# ProPrj.net
KiCad netlist of a schematic drawn in EasyEDA Pro
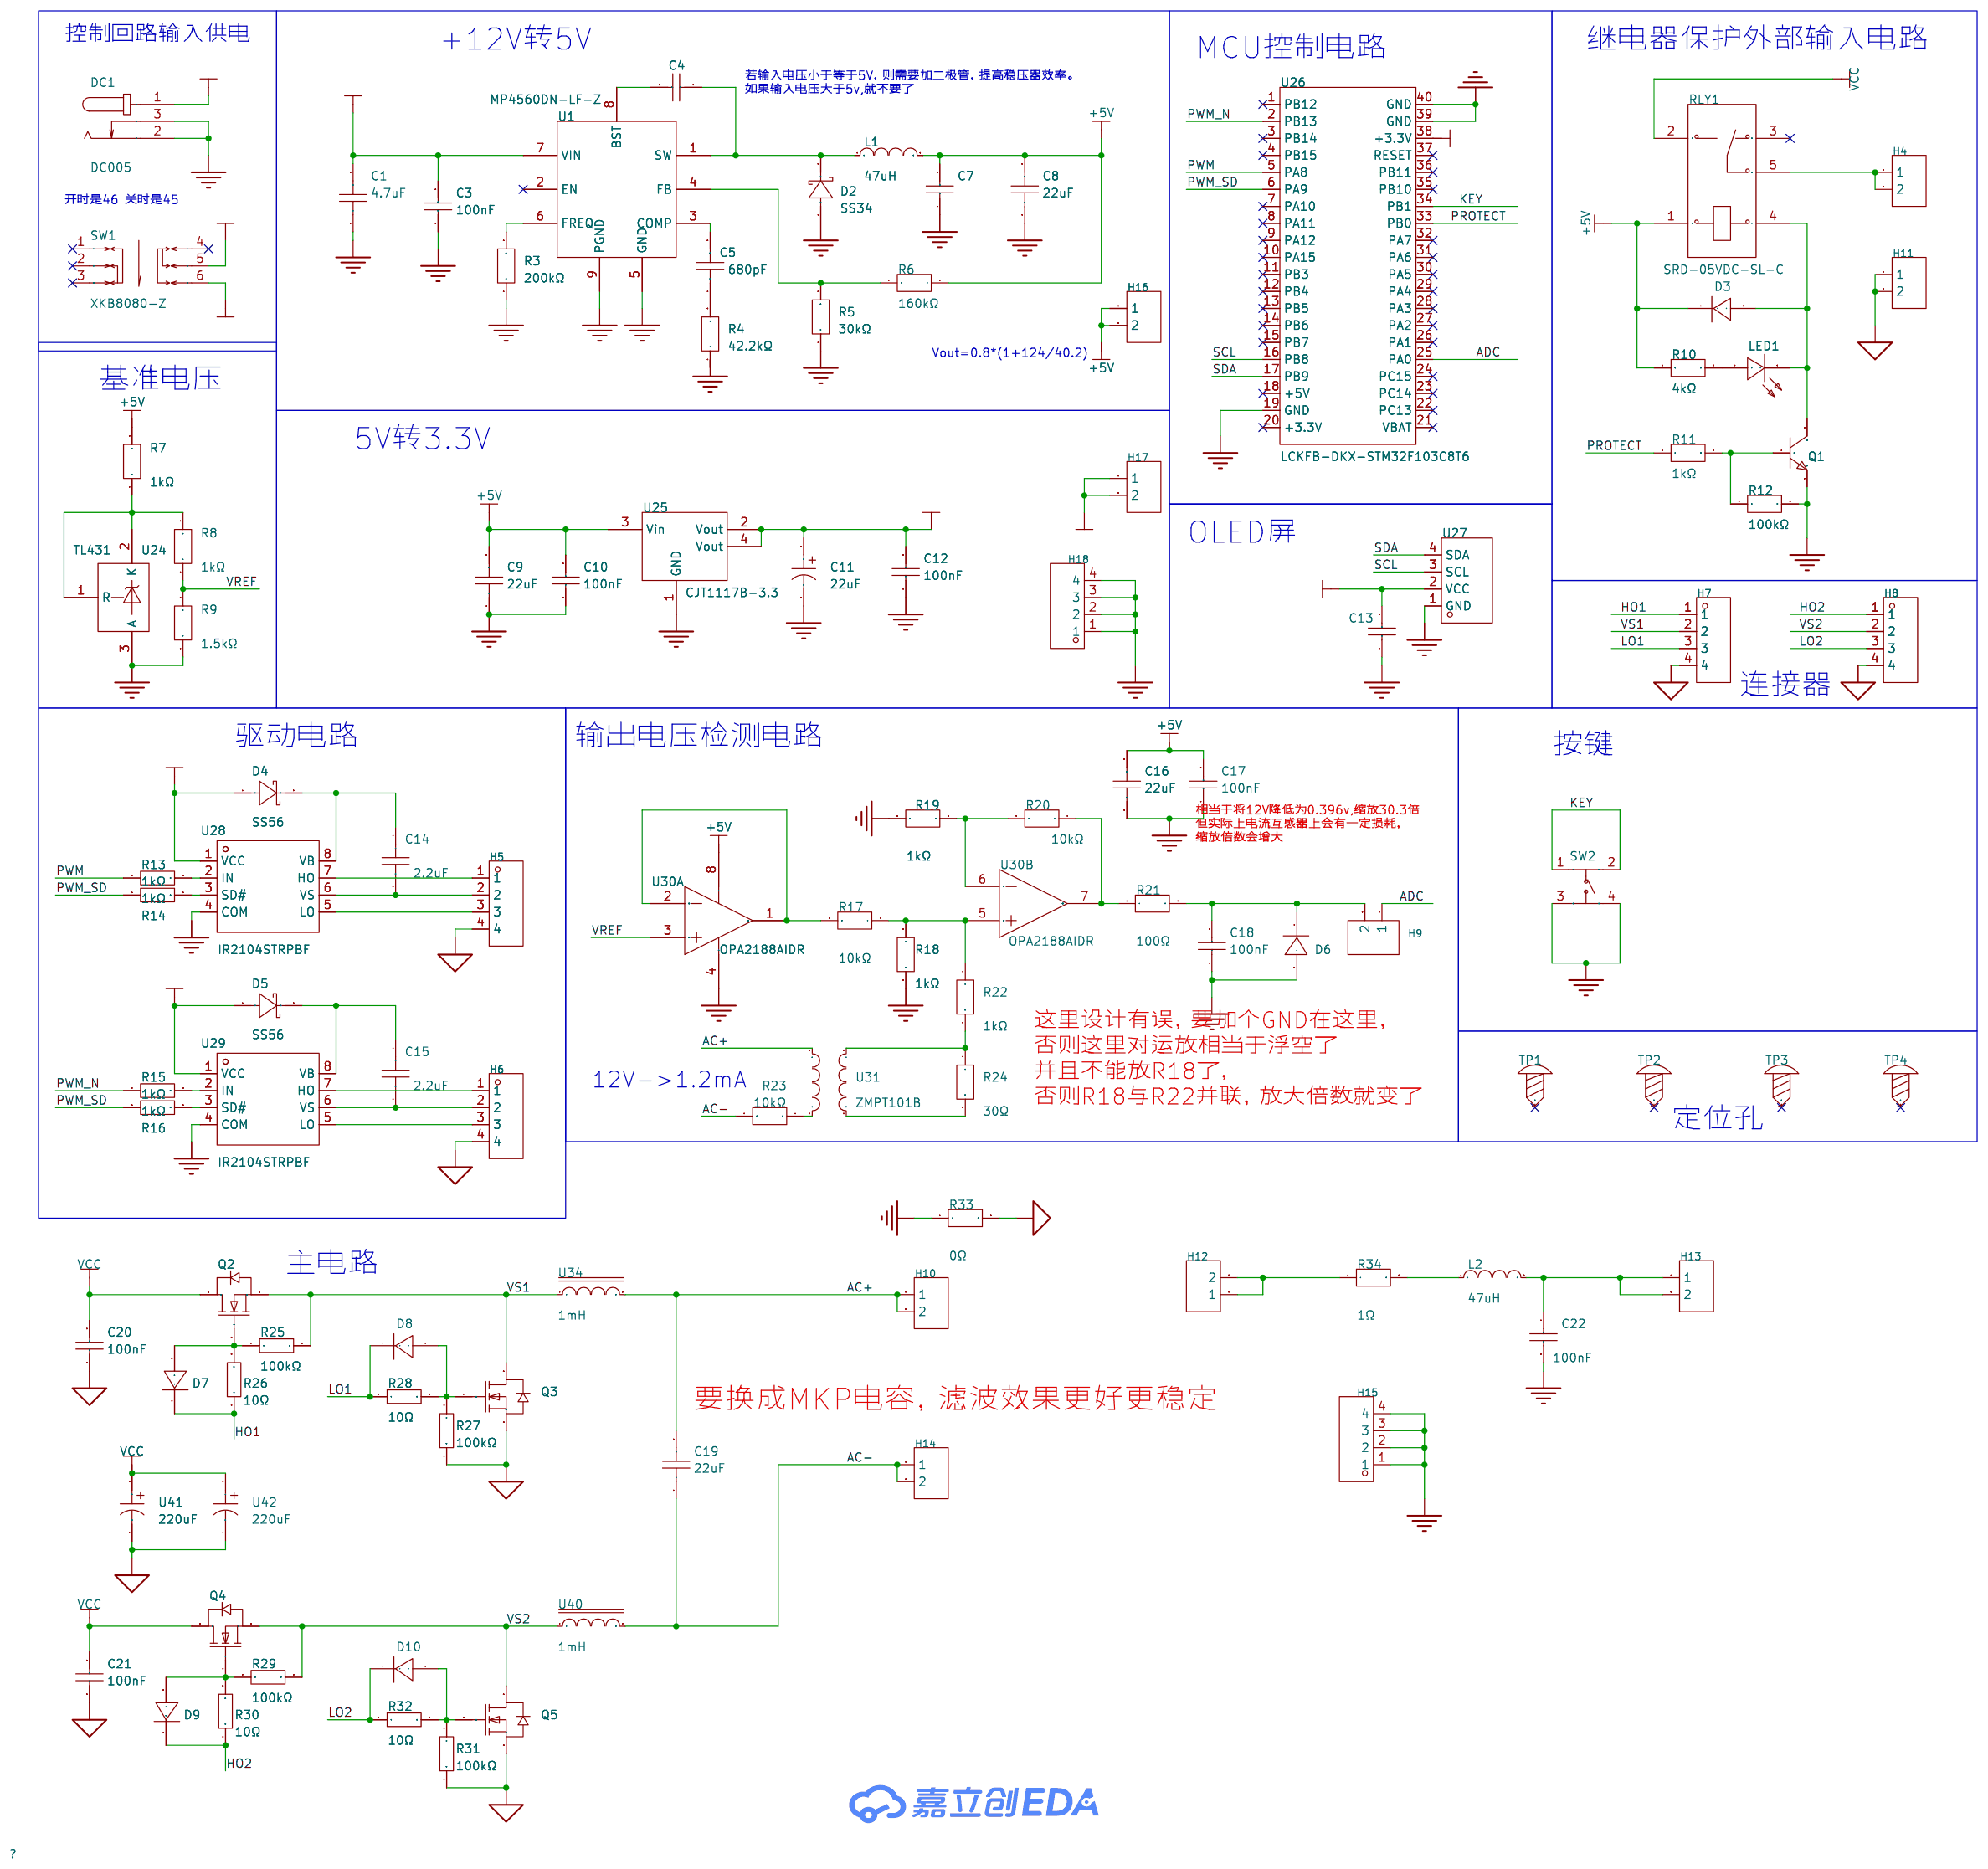
[diagram p0: schematic sheet]

(export (version "E")
  (design (tool "Eeschema 10.0.6"))
  (components
    (comp (ref "C1")
      (value "4.7uF")
      (footprint "easyedapro:C1206")
      (description "容值:4.7uF;精度:±10%;额定电压:100V;温度系数:X7R;")
      (fields
        (field (name "Manufacturer Part") "HHV1206R7475K101NSPJ")
        (field (name "Manufacturer") "Chinocera(华瓷)")
      )
      (libsource (lib "easyedapro") (part "HHV1206R7475K101NSPJ"))
    )
    (comp (ref "C3")
      (value "100nF")
      (footprint "easyedapro:C0805")
      (description "容值:100nF;精度:±10%;额定电压:100V;温度系数:X7R;")
      (fields
        (field (name "Manufacturer Part") "CL21B104KCFNNNE")
        (field (name "Manufacturer") "SAMSUNG(三星)")
      )
      (libsource (lib "easyedapro") (part "CL21B104KCFNNNE"))
    )
    (comp (ref "C4")
      (value "100nF")
      (footprint "easyedapro:C0805")
      (description "容值:100nF;精度:±10%;额定电压:100V;温度系数:X7R;")
      (fields
        (field (name "Manufacturer Part") "CL21B104KCFNNNE")
        (field (name "Manufacturer") "SAMSUNG(三星)")
      )
      (libsource (lib "easyedapro") (part "CL21B104KCFNNNE"))
    )
    (comp (ref "C5")
      (value "680pF")
      (footprint "easyedapro:C0805")
      (description "容值:680pF;精度:±10%;额定电压:100V;温度系数:X7R;")
      (fields
        (field (name "Manufacturer Part") "HHV0805R7681K101NTHJ")
        (field (name "Manufacturer") "Chinocera(华瓷)")
      )
      (libsource (lib "easyedapro") (part "HHV0805R7681K101NTHJ"))
    )
    (comp (ref "C7")
      (value "100nF")
      (footprint "easyedapro:C0805")
      (description "容值:100nF;精度:±10%;额定电压:100V;温度系数:X7R;")
      (fields
        (field (name "Manufacturer Part") "CL21B104KCFNNNE")
        (field (name "Manufacturer") "SAMSUNG(三星)")
      )
      (libsource (lib "easyedapro") (part "CL21B104KCFNNNE"))
    )
    (comp (ref "C8")
      (value "22uF")
      (footprint "easyedapro:C0805")
      (description "容值:22uF;精度:±20%;额定电压:35V;材质(温度系数):X5R;")
      (fields
        (field (name "Manufacturer Part") "CGA0805X5R226M350MT")
        (field (name "Manufacturer") "HRE(芯声)")
      )
      (libsource (lib "easyedapro") (part "CGA0805X5R226M350MT"))
    )
    (comp (ref "C9")
      (value "22uF")
      (footprint "easyedapro:C0805")
      (description "容值:22uF;精度:±20%;额定电压:35V;材质(温度系数):X5R;")
      (fields
        (field (name "Manufacturer Part") "CGA0805X5R226M350MT")
        (field (name "Manufacturer") "HRE(芯声)")
      )
      (libsource (lib "easyedapro") (part "CGA0805X5R226M350MT"))
    )
    (comp (ref "C10")
      (value "100nF")
      (footprint "easyedapro:C0805")
      (description "容值:100nF;精度:±10%;额定电压:100V;温度系数:X7R;")
      (fields
        (field (name "Manufacturer Part") "CL21B104KCFNNNE")
        (field (name "Manufacturer") "SAMSUNG(三星)")
      )
      (libsource (lib "easyedapro") (part "CL21B104KCFNNNE"))
    )
    (comp (ref "C11")
      (value "22uF")
      (footprint "easyedapro:CAP-TH_BD6.0-P2.54-D0.5-FD")
      (description "容值:22uF;精度:±10%;额定电压:25V;等效串联电阻(ESR):-;")
      (fields
        (field (name "Manufacturer Part") "199D226X9025D1V1E3")
        (field (name "Manufacturer") "VISHAY(威世)")
      )
      (libsource (lib "easyedapro") (part "199D226X9025D1V1E3"))
    )
    (comp (ref "C12")
      (value "100nF")
      (footprint "easyedapro:C0805")
      (description "容值:100nF;精度:±10%;额定电压:100V;温度系数:X7R;")
      (fields
        (field (name "Manufacturer Part") "CL21B104KCFNNNE")
        (field (name "Manufacturer") "SAMSUNG(三星)")
      )
      (libsource (lib "easyedapro") (part "CL21B104KCFNNNE"))
    )
    (comp (ref "C13")
      (value "100nF")
      (footprint "easyedapro:C0805")
      (description "容值:100nF;精度:±10%;额定电压:100V;温度系数:X7R;")
      (fields
        (field (name "Manufacturer Part") "CL21B104KCFNNNE")
        (field (name "Manufacturer") "SAMSUNG(三星)")
      )
      (libsource (lib "easyedapro") (part "CL21B104KCFNNNE"))
    )
    (comp (ref "C14")
      (value "2.2uF")
      (footprint "easyedapro:C0805")
      (description "容值:22uF;精度:±20%;额定电压:35V;材质(温度系数):X5R;")
      (fields
        (field (name "Manufacturer Part") "CGA0805X5R226M350MT")
        (field (name "Manufacturer") "HRE(芯声)")
      )
      (libsource (lib "easyedapro") (part "CGA0805X5R226M350MT"))
    )
    (comp (ref "C15")
      (value "2.2uF")
      (footprint "easyedapro:C0805")
      (description "容值:22uF;精度:±20%;额定电压:35V;材质(温度系数):X5R;")
      (fields
        (field (name "Manufacturer Part") "CGA0805X5R226M350MT")
        (field (name "Manufacturer") "HRE(芯声)")
      )
      (libsource (lib "easyedapro") (part "CGA0805X5R226M350MT"))
    )
    (comp (ref "C16")
      (value "22uF")
      (footprint "easyedapro:C0805")
      (description "容值:22uF;精度:±20%;额定电压:35V;材质(温度系数):X5R;")
      (fields
        (field (name "Manufacturer Part") "CGA0805X5R226M350MT")
        (field (name "Manufacturer") "HRE(芯声)")
      )
      (libsource (lib "easyedapro") (part "CGA0805X5R226M350MT"))
    )
    (comp (ref "C17")
      (value "100nF")
      (footprint "easyedapro:C0805")
      (description "容值:100nF;精度:±10%;额定电压:100V;温度系数:X7R;")
      (fields
        (field (name "Manufacturer Part") "CL21B104KCFNNNE")
        (field (name "Manufacturer") "SAMSUNG(三星)")
      )
      (libsource (lib "easyedapro") (part "CL21B104KCFNNNE"))
    )
    (comp (ref "C18")
      (value "100nF")
      (footprint "easyedapro:C0805")
      (description "容值:100nF;精度:±10%;额定电压:100V;温度系数:X7R;")
      (fields
        (field (name "Manufacturer Part") "CL21B104KCFNNNE")
        (field (name "Manufacturer") "SAMSUNG(三星)")
      )
      (libsource (lib "easyedapro") (part "CL21B104KCFNNNE"))
    )
    (comp (ref "C19")
      (value "22uF")
      (footprint "easyedapro:C0805")
      (description "容值:22uF;精度:±20%;额定电压:35V;材质(温度系数):X5R;")
      (fields
        (field (name "Manufacturer Part") "CGA0805X5R226M350MT")
        (field (name "Manufacturer") "HRE(芯声)")
      )
      (libsource (lib "easyedapro") (part "CGA0805X5R226M350MT"))
    )
    (comp (ref "C20")
      (value "100nF")
      (footprint "easyedapro:C0805")
      (description "容值:100nF;精度:±10%;额定电压:100V;温度系数:X7R;")
      (fields
        (field (name "Manufacturer Part") "CL21B104KCFNNNE")
        (field (name "Manufacturer") "SAMSUNG(三星)")
      )
      (libsource (lib "easyedapro") (part "CL21B104KCFNNNE"))
    )
    (comp (ref "C21")
      (value "100nF")
      (footprint "easyedapro:C0805")
      (description "容值:100nF;精度:±10%;额定电压:100V;温度系数:X7R;")
      (fields
        (field (name "Manufacturer Part") "CL21B104KCFNNNE")
        (field (name "Manufacturer") "SAMSUNG(三星)")
      )
      (libsource (lib "easyedapro") (part "CL21B104KCFNNNE"))
    )
    (comp (ref "C22")
      (value "100nF")
      (footprint "easyedapro:C0805")
      (description "容值:100nF;精度:±10%;额定电压:100V;温度系数:X7R;")
      (fields
        (field (name "Manufacturer Part") "CL21B104KCFNNNE")
        (field (name "Manufacturer") "SAMSUNG(三星)")
      )
      (libsource (lib "easyedapro") (part "CL21B104KCFNNNE"))
    )
    (comp (ref "D2")
      (value "SS34")
      (footprint "easyedapro:SMA_L4.3-W2.6-LS5.0-FD")
      (description "二极管配置:独立式;正向压降(Vf):550mV@3.0A;直流反向耐压(Vr):40V;整流电流:3A;")
      (fields (field (name "Manufacturer") "R+O(宏嘉诚)"))
      (libsource (lib "easyedapro") (part "SS34_C7420365"))
    )
    (comp (ref "D3")
      (value "1N4148W-E3-08")
      (footprint "easyedapro:SOD-123_L2.8-W1.8-LS3.7-RD")
      (description "二极管配置:1个独立式;正向压降(Vf):1.2V@100mA;直流反向耐压(Vr):75V;整流电流:150mA;反向恢复时间(Trr):4ns;")
      (fields (field (name "Manufacturer") "VISHAY(威世)"))
      (libsource (lib "easyedapro") (part "1N4148W-E3-08"))
    )
    (comp (ref "D4")
      (value "SS56")
      (footprint "easyedapro:SMA_L4.3-W2.6-LS5.0-FD")
      (description "二极管配置:独立式;正向压降(Vf):550mV@3.0A;直流反向耐压(Vr):40V;整流电流:3A;")
      (fields (field (name "Manufacturer") "R+O(宏嘉诚)"))
      (libsource (lib "easyedapro") (part "SS34_C7420365"))
    )
    (comp (ref "D5")
      (value "SS56")
      (footprint "easyedapro:SMA_L4.3-W2.6-LS5.0-FD")
      (description "二极管配置:独立式;正向压降(Vf):550mV@3.0A;直流反向耐压(Vr):40V;整流电流:3A;")
      (fields (field (name "Manufacturer") "R+O(宏嘉诚)"))
      (libsource (lib "easyedapro") (part "SS34_C7420365"))
    )
    (comp (ref "D6")
      (value "1N4148W-E3-08")
      (footprint "easyedapro:SOD-123_L2.8-W1.8-LS3.7-RD")
      (description "二极管配置:1个独立式;正向压降(Vf):1.2V@100mA;直流反向耐压(Vr):75V;整流电流:150mA;反向恢复时间(Trr):4ns;")
      (fields (field (name "Manufacturer") "VISHAY(威世)"))
      (libsource (lib "easyedapro") (part "1N4148W-E3-08"))
    )
    (comp (ref "D7")
      (value "1N4148W-E3-08")
      (footprint "easyedapro:SOD-123_L2.8-W1.8-LS3.7-RD")
      (description "二极管配置:1个独立式;正向压降(Vf):1.2V@100mA;直流反向耐压(Vr):75V;整流电流:150mA;反向恢复时间(Trr):4ns;")
      (fields (field (name "Manufacturer") "VISHAY(威世)"))
      (libsource (lib "easyedapro") (part "1N4148W-E3-08"))
    )
    (comp (ref "D8")
      (value "1N4148W-E3-08")
      (footprint "easyedapro:SOD-123_L2.8-W1.8-LS3.7-RD")
      (description "二极管配置:1个独立式;正向压降(Vf):1.2V@100mA;直流反向耐压(Vr):75V;整流电流:150mA;反向恢复时间(Trr):4ns;")
      (fields (field (name "Manufacturer") "VISHAY(威世)"))
      (libsource (lib "easyedapro") (part "1N4148W-E3-08"))
    )
    (comp (ref "D9")
      (value "1N4148W-E3-08")
      (footprint "easyedapro:SOD-123_L2.8-W1.8-LS3.7-RD")
      (description "二极管配置:1个独立式;正向压降(Vf):1.2V@100mA;直流反向耐压(Vr):75V;整流电流:150mA;反向恢复时间(Trr):4ns;")
      (fields (field (name "Manufacturer") "VISHAY(威世)"))
      (libsource (lib "easyedapro") (part "1N4148W-E3-08"))
    )
    (comp (ref "D10")
      (value "1N4148W-E3-08")
      (footprint "easyedapro:SOD-123_L2.8-W1.8-LS3.7-RD")
      (description "二极管配置:1个独立式;正向压降(Vf):1.2V@100mA;直流反向耐压(Vr):75V;整流电流:150mA;反向恢复时间(Trr):4ns;")
      (fields (field (name "Manufacturer") "VISHAY(威世)"))
      (libsource (lib "easyedapro") (part "1N4148W-E3-08"))
    )
    (comp (ref "DC1")
      (value "DC005")
      (footprint "easyedapro:DC-IN-TH_DC005")
      (description "连接器类型:DC电源插座;安装方式:弯插;触点内径:2mm;触点外径:6.3mm;额定电流:500mA;额定电压:30V;工作温度:-25°C~+70°C;")
      (fields (field (name "Manufacturer") "SHOU HAN(首韩)"))
      (libsource (lib "easyedapro") (part "DC005_C431533"))
    )
    (comp (ref "H4")
      (value "~")
      (footprint "easyedapro:HDR-TH_2P-P2.54-V-F")
      (libsource (lib "easyedapro") (part "Header-Female-2.54_1x2"))
    )
    (comp (ref "H5")
      (value "~")
      (footprint "easyedapro:HDR-TH_4P-P2.54-V-F")
      (libsource (lib "easyedapro") (part "2.54-1*4P母"))
    )
    (comp (ref "H6")
      (value "~")
      (footprint "easyedapro:HDR-TH_4P-P2.54-V-F")
      (libsource (lib "easyedapro") (part "2.54-1*4P母"))
    )
    (comp (ref "H7")
      (value "~")
      (footprint "easyedapro:HDR-TH_4P-P2.54-V-F")
      (libsource (lib "easyedapro") (part "2.54-1*4P母"))
    )
    (comp (ref "H8")
      (value "~")
      (footprint "easyedapro:HDR-TH_4P-P2.54-V-F")
      (libsource (lib "easyedapro") (part "2.54-1*4P母"))
    )
    (comp (ref "H9")
      (value "~")
      (footprint "easyedapro:HDR-TH_2P-P2.54-V-F")
      (libsource (lib "easyedapro") (part "Header-Female-2.54_1x2"))
    )
    (comp (ref "H10")
      (value "~")
      (footprint "easyedapro:HDR-TH_2P-P2.54-V-F")
      (libsource (lib "easyedapro") (part "Header-Female-2.54_1x2"))
    )
    (comp (ref "H11")
      (value "~")
      (footprint "easyedapro:HDR-TH_2P-P2.54-V-F")
      (libsource (lib "easyedapro") (part "Header-Female-2.54_1x2"))
    )
    (comp (ref "H12")
      (value "~")
      (footprint "easyedapro:HDR-TH_2P-P2.54-V-F")
      (libsource (lib "easyedapro") (part "Header-Female-2.54_1x2"))
    )
    (comp (ref "H13")
      (value "~")
      (footprint "easyedapro:HDR-TH_2P-P2.54-V-F")
      (libsource (lib "easyedapro") (part "Header-Female-2.54_1x2"))
    )
    (comp (ref "H14")
      (value "~")
      (footprint "easyedapro:HDR-TH_2P-P2.54-V-F")
      (libsource (lib "easyedapro") (part "Header-Female-2.54_1x2"))
    )
    (comp (ref "H15")
      (value "~")
      (footprint "easyedapro:HDR-TH_4P-P2.54-V-F")
      (libsource (lib "easyedapro") (part "2.54-1*4P母"))
    )
    (comp (ref "H16")
      (value "~")
      (footprint "easyedapro:HDR-TH_2P-P2.54-V-F")
      (libsource (lib "easyedapro") (part "Header-Female-2.54_1x2"))
    )
    (comp (ref "H17")
      (value "~")
      (footprint "easyedapro:HDR-TH_2P-P2.54-V-F")
      (libsource (lib "easyedapro") (part "Header-Female-2.54_1x2"))
    )
    (comp (ref "H18")
      (value "~")
      (footprint "easyedapro:HDR-TH_4P-P2.54-V-F")
      (libsource (lib "easyedapro") (part "2.54-1*4P母"))
    )
    (comp (ref "L1")
      (value "47uH")
      (footprint "easyedapro:IND-SMD_L7.0-W7.0_SMDRS70XX")
      (description "电感值:47uH;精度:±20%;额定电流:920mA;")
      (fields
        (field (name "Manufacturer Part") "SLP7045S470MTT")
        (field (name "Manufacturer") "Sunltech(顺磁)")
      )
      (libsource (lib "easyedapro") (part "SLP7045S470MTT"))
    )
    (comp (ref "L2")
      (value "47uH")
      (footprint "easyedapro:IND-SMD_L7.0-W7.0_SMDRS70XX")
      (description "电感值:47uH;精度:±20%;额定电流:920mA;")
      (fields
        (field (name "Manufacturer Part") "SLP7045S470MTT")
        (field (name "Manufacturer") "Sunltech(顺磁)")
      )
      (libsource (lib "easyedapro") (part "SLP7045S470MTT"))
    )
    (comp (ref "LED1")
      (value "NCD0805R1")
      (footprint "easyedapro:LED0805-R-RD")
      (fields (field (name "Manufacturer") "国星光电"))
      (libsource (lib "easyedapro") (part "FC-2012HRK-620D"))
    )
    (comp (ref "Q1")
      (value "MMS9013-H-TP")
      (footprint "easyedapro:SOT-23-3_L2.9-W1.3-P1.90-LS2.4-BR")
      (description "晶体管类型:NPN;集电极电流(Ic):500mA;集射极击穿电压(Vceo):25V;耗散功率(Pd):300mW;")
      (fields (field (name "Manufacturer") "MCC(美微科)"))
      (libsource (lib "easyedapro") (part "MMS9013-H-TP"))
    )
    (comp (ref "Q2")
      (value "IRF3205ZPBF")
      (footprint "easyedapro:TO-220-3_L10.0-W4.5-P2.54-T")
      (fields (field (name "Manufacturer") "Infineon(英飞凌)"))
      (libsource (lib "easyedapro") (part "IRF3205ZPBF"))
    )
    (comp (ref "Q3")
      (value "IRF3205ZPBF")
      (footprint "easyedapro:TO-220-3_L10.0-W4.5-P2.54-T")
      (fields (field (name "Manufacturer") "Infineon(英飞凌)"))
      (libsource (lib "easyedapro") (part "IRF3205ZPBF"))
    )
    (comp (ref "Q4")
      (value "IRF3205ZPBF")
      (footprint "easyedapro:TO-220-3_L10.0-W4.5-P2.54-T")
      (fields (field (name "Manufacturer") "Infineon(英飞凌)"))
      (libsource (lib "easyedapro") (part "IRF3205ZPBF"))
    )
    (comp (ref "Q5")
      (value "IRF3205ZPBF")
      (footprint "easyedapro:TO-220-3_L10.0-W4.5-P2.54-T")
      (fields (field (name "Manufacturer") "Infineon(英飞凌)"))
      (libsource (lib "easyedapro") (part "IRF3205ZPBF"))
    )
    (comp (ref "R3")
      (value "200kΩ")
      (footprint "easyedapro:R0805")
      (description "电阻类型:厚膜电阻;阻值:200kΩ;精度:±1%;功率:125mW;工作电压:150V;温度系数:±100ppm/°C;")
      (fields (field (name "Manufacturer Part") "FRC0805F2003TS") (field (name "Manufacturer") "FOJAN(富捷)"))
      (libsource (lib "easyedapro") (part "FRC0805F2003TS"))
    )
    (comp (ref "R4")
      (value "42.2kΩ")
      (footprint "easyedapro:R0805")
      (description "电阻类型:厚膜电阻;阻值:42.2kΩ;精度:±1%;功率:125mW;工作电压:150V;温度系数:±100ppm/°C;")
      (fields (field (name "Manufacturer Part") "FRC0805F4222TS") (field (name "Manufacturer") "FOJAN(富捷)"))
      (libsource (lib "easyedapro") (part "FRC0805F4222TS"))
    )
    (comp (ref "R5")
      (value "30kΩ")
      (footprint "easyedapro:R0805")
      (description "电阻类型:厚膜电阻;阻值:40.2kΩ;精度:±1%;功率:125mW;工作电压:150V;温度系数:±100ppm/°C;")
      (fields (field (name "Manufacturer Part") "FRC0805F4022TS") (field (name "Manufacturer") "FOJAN(富捷)"))
      (libsource (lib "easyedapro") (part "FRC0805F4022TS"))
    )
    (comp (ref "R6")
      (value "160kΩ")
      (footprint "easyedapro:R0805")
      (description "电阻类型:厚膜电阻;阻值:124kΩ;精度:±1%;功率:125mW;工作电压:150V;温度系数:±100ppm/°C;")
      (fields (field (name "Manufacturer Part") "FRC0805F1243TS") (field (name "Manufacturer") "FOJAN(富捷)"))
      (libsource (lib "easyedapro") (part "FRC0805F1243TS"))
    )
    (comp (ref "R7")
      (value "1kΩ")
      (footprint "easyedapro:R0805")
      (description "电阻类型:厚膜电阻;阻值:124kΩ;精度:±1%;功率:125mW;工作电压:150V;温度系数:±100ppm/°C;")
      (fields (field (name "Manufacturer Part") "FRC0805F1243TS") (field (name "Manufacturer") "FOJAN(富捷)"))
      (libsource (lib "easyedapro") (part "FRC0805F1243TS"))
    )
    (comp (ref "R8")
      (value "1kΩ")
      (footprint "easyedapro:R0805")
      (description "电阻类型:厚膜电阻;阻值:124kΩ;精度:±1%;功率:125mW;工作电压:150V;温度系数:±100ppm/°C;")
      (fields (field (name "Manufacturer Part") "FRC0805F1243TS") (field (name "Manufacturer") "FOJAN(富捷)"))
      (libsource (lib "easyedapro") (part "FRC0805F1243TS"))
    )
    (comp (ref "R9")
      (value "1.5kΩ")
      (footprint "easyedapro:R0805")
      (description "电阻类型:厚膜电阻;阻值:124kΩ;精度:±1%;功率:125mW;工作电压:150V;温度系数:±100ppm/°C;")
      (fields (field (name "Manufacturer Part") "FRC0805F1243TS") (field (name "Manufacturer") "FOJAN(富捷)"))
      (libsource (lib "easyedapro") (part "FRC0805F1243TS"))
    )
    (comp (ref "R10")
      (value "4kΩ")
      (footprint "easyedapro:R0805")
      (description "电阻类型:厚膜电阻;阻值:124kΩ;精度:±1%;功率:125mW;工作电压:150V;温度系数:±100ppm/°C;")
      (fields (field (name "Manufacturer Part") "FRC0805F1243TS") (field (name "Manufacturer") "FOJAN(富捷)"))
      (libsource (lib "easyedapro") (part "FRC0805F1243TS"))
    )
    (comp (ref "R11")
      (value "1kΩ")
      (footprint "easyedapro:R0805")
      (description "电阻类型:厚膜电阻;阻值:124kΩ;精度:±1%;功率:125mW;工作电压:150V;温度系数:±100ppm/°C;")
      (fields (field (name "Manufacturer Part") "FRC0805F1243TS") (field (name "Manufacturer") "FOJAN(富捷)"))
      (libsource (lib "easyedapro") (part "FRC0805F1243TS"))
    )
    (comp (ref "R12")
      (value "100kΩ")
      (footprint "easyedapro:R0805")
      (description "电阻类型:厚膜电阻;阻值:124kΩ;精度:±1%;功率:125mW;工作电压:150V;温度系数:±100ppm/°C;")
      (fields (field (name "Manufacturer Part") "FRC0805F1243TS") (field (name "Manufacturer") "FOJAN(富捷)"))
      (libsource (lib "easyedapro") (part "FRC0805F1243TS"))
    )
    (comp (ref "R13")
      (value "1kΩ")
      (footprint "easyedapro:R1206")
      (description "电阻类型:厚膜电阻;阻值:1kΩ;精度:±1%;功率:250mW;工作电压:200V;温度系数:±100ppm/°C;")
      (fields
        (field (name "Manufacturer Part") "1206W4F1001T5E")
        (field (name "Manufacturer") "UNI-ROYAL(厚声)")
      )
      (libsource (lib "easyedapro") (part "1206W4F1001T5E"))
    )
    (comp (ref "R14")
      (value "1kΩ")
      (footprint "easyedapro:R1206")
      (description "电阻类型:厚膜电阻;阻值:1kΩ;精度:±1%;功率:250mW;工作电压:200V;温度系数:±100ppm/°C;")
      (fields
        (field (name "Manufacturer Part") "1206W4F1001T5E")
        (field (name "Manufacturer") "UNI-ROYAL(厚声)")
      )
      (libsource (lib "easyedapro") (part "1206W4F1001T5E"))
    )
    (comp (ref "R15")
      (value "1kΩ")
      (footprint "easyedapro:R1206")
      (description "电阻类型:厚膜电阻;阻值:1kΩ;精度:±1%;功率:250mW;工作电压:200V;温度系数:±100ppm/°C;")
      (fields
        (field (name "Manufacturer Part") "1206W4F1001T5E")
        (field (name "Manufacturer") "UNI-ROYAL(厚声)")
      )
      (libsource (lib "easyedapro") (part "1206W4F1001T5E"))
    )
    (comp (ref "R16")
      (value "1kΩ")
      (footprint "easyedapro:R1206")
      (description "电阻类型:厚膜电阻;阻值:1kΩ;精度:±1%;功率:250mW;工作电压:200V;温度系数:±100ppm/°C;")
      (fields
        (field (name "Manufacturer Part") "1206W4F1001T5E")
        (field (name "Manufacturer") "UNI-ROYAL(厚声)")
      )
      (libsource (lib "easyedapro") (part "1206W4F1001T5E"))
    )
    (comp (ref "R17")
      (value "10kΩ")
      (footprint "easyedapro:R0805")
      (description "电阻类型:厚膜电阻;阻值:124kΩ;精度:±1%;功率:125mW;工作电压:150V;温度系数:±100ppm/°C;")
      (fields (field (name "Manufacturer Part") "FRC0805F1243TS") (field (name "Manufacturer") "FOJAN(富捷)"))
      (libsource (lib "easyedapro") (part "FRC0805F1243TS"))
    )
    (comp (ref "R18")
      (value "1kΩ")
      (footprint "easyedapro:R0805")
      (description "电阻类型:厚膜电阻;阻值:124kΩ;精度:±1%;功率:125mW;工作电压:150V;温度系数:±100ppm/°C;")
      (fields (field (name "Manufacturer Part") "FRC0805F1243TS") (field (name "Manufacturer") "FOJAN(富捷)"))
      (libsource (lib "easyedapro") (part "FRC0805F1243TS"))
    )
    (comp (ref "R19")
      (value "1kΩ")
      (footprint "easyedapro:R0805")
      (description "电阻类型:厚膜电阻;阻值:124kΩ;精度:±1%;功率:125mW;工作电压:150V;温度系数:±100ppm/°C;")
      (fields (field (name "Manufacturer Part") "FRC0805F1243TS") (field (name "Manufacturer") "FOJAN(富捷)"))
      (libsource (lib "easyedapro") (part "FRC0805F1243TS"))
    )
    (comp (ref "R20")
      (value "10kΩ")
      (footprint "easyedapro:R0805")
      (description "电阻类型:厚膜电阻;阻值:124kΩ;精度:±1%;功率:125mW;工作电压:150V;温度系数:±100ppm/°C;")
      (fields (field (name "Manufacturer Part") "FRC0805F1243TS") (field (name "Manufacturer") "FOJAN(富捷)"))
      (libsource (lib "easyedapro") (part "FRC0805F1243TS"))
    )
    (comp (ref "R21")
      (value "100Ω")
      (footprint "easyedapro:R0805")
      (description "电阻类型:厚膜电阻;阻值:124kΩ;精度:±1%;功率:125mW;工作电压:150V;温度系数:±100ppm/°C;")
      (fields (field (name "Manufacturer Part") "FRC0805F1243TS") (field (name "Manufacturer") "FOJAN(富捷)"))
      (libsource (lib "easyedapro") (part "FRC0805F1243TS"))
    )
    (comp (ref "R22")
      (value "1kΩ")
      (footprint "easyedapro:R0805")
      (description "电阻类型:厚膜电阻;阻值:124kΩ;精度:±1%;功率:125mW;工作电压:150V;温度系数:±100ppm/°C;")
      (fields (field (name "Manufacturer Part") "FRC0805F1243TS") (field (name "Manufacturer") "FOJAN(富捷)"))
      (libsource (lib "easyedapro") (part "FRC0805F1243TS"))
    )
    (comp (ref "R23")
      (value "10kΩ")
      (footprint "easyedapro:R0805")
      (description "电阻类型:厚膜电阻;阻值:124kΩ;精度:±1%;功率:125mW;工作电压:150V;温度系数:±100ppm/°C;")
      (fields (field (name "Manufacturer Part") "FRC0805F1243TS") (field (name "Manufacturer") "FOJAN(富捷)"))
      (libsource (lib "easyedapro") (part "FRC0805F1243TS"))
    )
    (comp (ref "R24")
      (value "30Ω")
      (footprint "easyedapro:R0805")
      (description "电阻类型:厚膜电阻;阻值:124kΩ;精度:±1%;功率:125mW;工作电压:150V;温度系数:±100ppm/°C;")
      (fields (field (name "Manufacturer Part") "FRC0805F1243TS") (field (name "Manufacturer") "FOJAN(富捷)"))
      (libsource (lib "easyedapro") (part "FRC0805F1243TS"))
    )
    (comp (ref "R25")
      (value "100kΩ")
      (footprint "easyedapro:R1206")
      (description "电阻类型:厚膜电阻;阻值:1kΩ;精度:±1%;功率:250mW;工作电压:200V;温度系数:±100ppm/°C;")
      (fields
        (field (name "Manufacturer Part") "1206W4F1001T5E")
        (field (name "Manufacturer") "UNI-ROYAL(厚声)")
      )
      (libsource (lib "easyedapro") (part "1206W4F1001T5E"))
    )
    (comp (ref "R26")
      (value "10Ω")
      (footprint "easyedapro:R1206")
      (description "电阻类型:厚膜电阻;阻值:1kΩ;精度:±1%;功率:250mW;工作电压:200V;温度系数:±100ppm/°C;")
      (fields
        (field (name "Manufacturer Part") "1206W4F1001T5E")
        (field (name "Manufacturer") "UNI-ROYAL(厚声)")
      )
      (libsource (lib "easyedapro") (part "1206W4F1001T5E"))
    )
    (comp (ref "R27")
      (value "100kΩ")
      (footprint "easyedapro:R1206")
      (description "电阻类型:厚膜电阻;阻值:1kΩ;精度:±1%;功率:250mW;工作电压:200V;温度系数:±100ppm/°C;")
      (fields
        (field (name "Manufacturer Part") "1206W4F1001T5E")
        (field (name "Manufacturer") "UNI-ROYAL(厚声)")
      )
      (libsource (lib "easyedapro") (part "1206W4F1001T5E"))
    )
    (comp (ref "R28")
      (value "10Ω")
      (footprint "easyedapro:R1206")
      (description "电阻类型:厚膜电阻;阻值:1kΩ;精度:±1%;功率:250mW;工作电压:200V;温度系数:±100ppm/°C;")
      (fields
        (field (name "Manufacturer Part") "1206W4F1001T5E")
        (field (name "Manufacturer") "UNI-ROYAL(厚声)")
      )
      (libsource (lib "easyedapro") (part "1206W4F1001T5E"))
    )
    (comp (ref "R29")
      (value "100kΩ")
      (footprint "easyedapro:R1206")
      (description "电阻类型:厚膜电阻;阻值:1kΩ;精度:±1%;功率:250mW;工作电压:200V;温度系数:±100ppm/°C;")
      (fields
        (field (name "Manufacturer Part") "1206W4F1001T5E")
        (field (name "Manufacturer") "UNI-ROYAL(厚声)")
      )
      (libsource (lib "easyedapro") (part "1206W4F1001T5E"))
    )
    (comp (ref "R30")
      (value "10Ω")
      (footprint "easyedapro:R1206")
      (description "电阻类型:厚膜电阻;阻值:1kΩ;精度:±1%;功率:250mW;工作电压:200V;温度系数:±100ppm/°C;")
      (fields
        (field (name "Manufacturer Part") "1206W4F1001T5E")
        (field (name "Manufacturer") "UNI-ROYAL(厚声)")
      )
      (libsource (lib "easyedapro") (part "1206W4F1001T5E"))
    )
    (comp (ref "R31")
      (value "100kΩ")
      (footprint "easyedapro:R1206")
      (description "电阻类型:厚膜电阻;阻值:1kΩ;精度:±1%;功率:250mW;工作电压:200V;温度系数:±100ppm/°C;")
      (fields
        (field (name "Manufacturer Part") "1206W4F1001T5E")
        (field (name "Manufacturer") "UNI-ROYAL(厚声)")
      )
      (libsource (lib "easyedapro") (part "1206W4F1001T5E"))
    )
    (comp (ref "R32")
      (value "10Ω")
      (footprint "easyedapro:R1206")
      (description "电阻类型:厚膜电阻;阻值:1kΩ;精度:±1%;功率:250mW;工作电压:200V;温度系数:±100ppm/°C;")
      (fields
        (field (name "Manufacturer Part") "1206W4F1001T5E")
        (field (name "Manufacturer") "UNI-ROYAL(厚声)")
      )
      (libsource (lib "easyedapro") (part "1206W4F1001T5E"))
    )
    (comp (ref "R33")
      (value "0Ω")
      (footprint "easyedapro:R0805")
      (description "电阻类型:厚膜电阻;阻值:124kΩ;精度:±1%;功率:125mW;工作电压:150V;温度系数:±100ppm/°C;")
      (fields (field (name "Manufacturer Part") "FRC0805F1243TS") (field (name "Manufacturer") "FOJAN(富捷)"))
      (libsource (lib "easyedapro") (part "FRC0805F1243TS"))
    )
    (comp (ref "R34")
      (value "1Ω")
      (footprint "easyedapro:R0805")
      (description "电阻类型:厚膜电阻;阻值:124kΩ;精度:±1%;功率:125mW;工作电压:150V;温度系数:±100ppm/°C;")
      (fields (field (name "Manufacturer Part") "FRC0805F1243TS") (field (name "Manufacturer") "FOJAN(富捷)"))
      (libsource (lib "easyedapro") (part "FRC0805F1243TS"))
    )
    (comp (ref "RLY1")
      (value "SRD-05VDC-SL-C")
      (footprint "easyedapro:RELAY-TH_SRD-XXVDC-XL-C")
      (description "线圈电压:5V;触点形式:一组转换:1C(单刀双掷-转换);触点容量(电阻负载):-;最大切换电压:250V@AC;最大切换电流:15A;")
      (fields (field (name "Manufacturer") "松乐"))
      (libsource (lib "easyedapro") (part "SRD-05VDC-SL-C"))
    )
    (comp (ref "SW1")
      (value "XKB8080-Z")
      (footprint "easyedapro:SW-TH_6P-L8.0-W8.0-P2.50")
      (description "自锁/无锁:自锁;安装方式:直插;触点电流:100mA;额定电压:30V;带灯:不带;作用力:1.6N;工作寿命:10万次;")
      (fields (field (name "Manufacturer") "XKB Connection(中国星坤)"))
      (libsource (lib "easyedapro") (part "XKB8080-Z"))
    )
    (comp (ref "SW2")
      (value "TC-00104-050E")
      (footprint "easyedapro:SW-TH_4P-L6.0-W6.0-P4.50-LS6.5")
      (description "电路结构:单刀单掷;按钮形状:圆形按钮;作用力:2.5N;开关长度:6mm;开关宽度:6mm;开关高度:5mm;带支架:不带支架;带灯:无;工作寿命:-;")
      (fields (field (name "Manufacturer") "HOOYA(皓宇电子)"))
      (libsource (lib "easyedapro") (part "TC-00104-050E"))
    )
    (comp (ref "TP1") (value "~") (footprint "easyedapro:M3螺丝") (libsource (lib "easyedapro") (part "螺丝孔")))
    (comp (ref "TP2") (value "~") (footprint "easyedapro:M3螺丝") (libsource (lib "easyedapro") (part "螺丝孔")))
    (comp (ref "TP3") (value "~") (footprint "easyedapro:M3螺丝") (libsource (lib "easyedapro") (part "螺丝孔")))
    (comp (ref "TP4") (value "~") (footprint "easyedapro:M3螺丝") (libsource (lib "easyedapro") (part "螺丝孔")))
    (comp (ref "U1")
      (value "MP4560DN-LF-Z")
      (footprint "easyedapro:SOIC-8_L4.9-W3.9-P1.27-LS6.0-BL-EP3.1-1")
      (description "功能类型:降压型;输出类型:可调;工作电压:3.8V~55V;输出电压:800mV~52V;输出电流:2A;")
      (fields (field (name "Manufacturer") "MPS(芯源)"))
      (libsource (lib "easyedapro") (part "MP4560DN–LF–Z"))
    )
    (comp (ref "U24")
      (value "TL431")
      (footprint "easyedapro:SOT-23-3_L2.9-W1.4-P1.90-LS2.6-BR")
      (description "输出类型:可调;输入电压:37V;输出电压:2.5V~36V;输出电流:-;精度:-;")
      (fields (field (name "Manufacturer") "JSMSEMI(杰盛微)"))
      (libsource (lib "easyedapro") (part "TL431_C963380"))
    )
    (comp (ref "U25")
      (value "CJT1117B-3.3")
      (footprint "easyedapro:SOT-223-4_L6.5-W3.5-P2.30-LS7.0-BR")
      (description "输出类型:固定;工作电压:15V;输出电压:3.3V;输出电流:1A;电源纹波抑制比(PSRR):75dB@(120Hz);输出极性:正极;")
      (fields (field (name "Manufacturer") "CJ(江苏长电/长晶)"))
      (libsource (lib "easyedapro") (part "CJT1117B-3.3"))
    )
    (comp (ref "U26")
      (value "LCKFB-DKX-STM32F103C8T6")
      (footprint "easyedapro:CONN-TH_L53.3-W22.9_STM32F103C8T6-CARD")
      (fields (field (name "Manufacturer") "立创开发板"))
      (libsource (lib "easyedapro") (part "LCKFB-DKX-STM32F103C8T6"))
    )
    (comp (ref "U27")
      (value "HS96L03W2C03")
      (footprint "easyedapro:OLED-TH_L27.8-W27.2-P2.54_C9900033791")
      (description "主控芯片:SSD1315;接口类型:I2C;尺寸(inch):0.96;像素分辨率:128x64;")
      (fields (field (name "Manufacturer") "HS(汉昇)"))
      (libsource (lib "easyedapro") (part "HS96L03W2C03"))
    )
    (comp (ref "U28")
      (value "IR2104STRPBF")
      (footprint "easyedapro:SOIC-8_L4.9-W3.9-P1.27-LS6.0-BL")
      (fields (field (name "Manufacturer") "Infineon(英飞凌)"))
      (libsource (lib "easyedapro") (part "IR2104STRPBF"))
    )
    (comp (ref "U29")
      (value "IR2104STRPBF")
      (footprint "easyedapro:SOIC-8_L4.9-W3.9-P1.27-LS6.0-BL")
      (fields (field (name "Manufacturer") "Infineon(英飞凌)"))
      (libsource (lib "easyedapro") (part "IR2104STRPBF"))
    )
    (comp (ref "U30")
      (value "OPA2188AIDR")
      (footprint "easyedapro:SOIC-8_L4.9-W3.9-P1.27-LS6.0-BL")
      (description "放大器数:双路;增益带宽积(GBP):2MHz;输入偏置电流(Ib):160pA;输入失调电压(Vos):6uV;压摆率(SR):0.8V/us;轨到轨:轨到轨输出;")
      (fields (field (name "Manufacturer") "TI(德州仪器)"))
      (libsource (lib "easyedapro") (part "OPA2188AIDR"))
    )
    (comp (ref "U31")
      (value "ZMPT101B")
      (footprint "easyedapro:XFMR-TH_ZMPT101B")
      (description "匝数比:-;额定输入电流:-;次级侧电感值:-;")
      (fields (field (name "Manufacturer") "择明朗熙"))
      (libsource (lib "easyedapro") (part "ZMPT101B"))
    )
    (comp (ref "U34")
      (value "1mH")
      (footprint "easyedapro:IND-TH_L33.0-W15.6-P15.00-D1.5")
      (description "电感值:47uH;精度:±10%;额定电流:12A;类型:磁环电感;")
      (fields (field (name "Manufacturer Part") "XR106125TS470MV1L5") (field (name "Manufacturer") "XR(祥如)"))
      (libsource (lib "easyedapro") (part "XR106125TS470MV1L5"))
    )
    (comp (ref "U40")
      (value "1mH")
      (footprint "easyedapro:IND-TH_L33.0-W15.6-P15.00-D1.5")
      (description "电感值:47uH;精度:±10%;额定电流:12A;类型:磁环电感;")
      (fields (field (name "Manufacturer Part") "XR106125TS470MV1L5") (field (name "Manufacturer") "XR(祥如)"))
      (libsource (lib "easyedapro") (part "XR106125TS470MV1L5"))
    )
    (comp (ref "U41")
      (value "220uF")
      (footprint "easyedapro:CAP-TH_BD6.3-P2.50-D0.5-FD")
      (description "容值:220uF;精度:±20%;额定电压:25V;纹波电流:236mA@120kHz;等效串联电阻(ESR):-;")
      (fields (field (name "Manufacturer Part") "KM1E221M0611") (field (name "Manufacturer") "ROQANG(容强)"))
      (libsource (lib "easyedapro") (part "KM1E221M0611"))
    )
    (comp (ref "U42")
      (value "220uF")
      (footprint "easyedapro:CAP-TH_BD6.3-P2.50-D0.5-FD")
      (description "容值:220uF;精度:±20%;额定电压:25V;纹波电流:236mA@120kHz;等效串联电阻(ESR):-;")
      (fields (field (name "Manufacturer Part") "KM1E221M0611") (field (name "Manufacturer") "ROQANG(容强)"))
      (libsource (lib "easyedapro") (part "KM1E221M0611"))
    )
  )
  (nets
    (net (code "1") (name "+3.3V") (class "Default")
      (node (ref "C11") (pin "1") (pinfunction "1_1") (pintype "input"))
      (node (ref "C12") (pin "2") (pinfunction "2_2") (pintype "input"))
      (node (ref "C13") (pin "2") (pinfunction "2_2") (pintype "input"))
      (node (ref "H17") (pin "1") (pinfunction "1_1") (pintype "input"))
      (node (ref "H17") (pin "2") (pinfunction "2_2") (pintype "input"))
      (node (ref "U25") (pin "2") (pinfunction "Vout_2") (pintype "unspecified"))
      (node (ref "U25") (pin "4") (pinfunction "Vout_4") (pintype "unspecified"))
      (node (ref "U26") (pin "38") (pinfunction "+3.3V_38") (pintype "unspecified"))
      (node (ref "U27") (pin "2") (pinfunction "VCC_2") (pintype "unspecified"))
    )
    (net (code "2") (name "+5V") (class "Default")
      (node (ref "C10") (pin "2") (pinfunction "2_2") (pintype "input"))
      (node (ref "C16") (pin "2") (pinfunction "2_2") (pintype "unspecified"))
      (node (ref "C17") (pin "2") (pinfunction "2_2") (pintype "input"))
      (node (ref "C7") (pin "2") (pinfunction "2_2") (pintype "input"))
      (node (ref "C8") (pin "2") (pinfunction "2_2") (pintype "unspecified"))
      (node (ref "C9") (pin "2") (pinfunction "2_2") (pintype "unspecified"))
      (node (ref "D3") (pin "1") (pinfunction "K_1") (pintype "unspecified"))
      (node (ref "H16") (pin "1") (pinfunction "1_1") (pintype "input"))
      (node (ref "H16") (pin "2") (pinfunction "2_2") (pintype "input"))
      (node (ref "L1") (pin "2") (pinfunction "2_2") (pintype "unspecified"))
      (node (ref "R10") (pin "1") (pinfunction "1_1") (pintype "unspecified"))
      (node (ref "R6") (pin "2") (pinfunction "2_2") (pintype "unspecified"))
      (node (ref "R7") (pin "2") (pinfunction "2_2") (pintype "unspecified"))
      (node (ref "RLY1") (pin "1") (pinfunction "1_1") (pintype "input"))
      (node (ref "U25") (pin "3") (pinfunction "Vin_3") (pintype "unspecified"))
      (node (ref "U30") (pin "8") (pinfunction "V+_8") (pintype "unspecified"))
    )
    (net (code "3") (name "+12V") (class "Default")
      (node (ref "C1") (pin "2") (pinfunction "2_2") (pintype "unspecified"))
      (node (ref "C3") (pin "2") (pinfunction "2_2") (pintype "input"))
      (node (ref "D4") (pin "1") (pinfunction "A_1") (pintype "unspecified"))
      (node (ref "D5") (pin "1") (pinfunction "A_1") (pintype "unspecified"))
      (node (ref "SW1") (pin "5") (pinfunction "5_5") (pintype "unspecified"))
      (node (ref "U1") (pin "7") (pinfunction "VIN_7") (pintype "unspecified"))
      (node (ref "U28") (pin "1") (pinfunction "VCC_1") (pintype "unspecified"))
      (node (ref "U29") (pin "1") (pinfunction "VCC_1") (pintype "unspecified"))
    )
    (net (code "4") (name "/AC+") (class "Default")
      (node (ref "C19") (pin "2") (pinfunction "2_2") (pintype "unspecified"))
      (node (ref "H10") (pin "1") (pinfunction "1_1") (pintype "input"))
      (node (ref "H10") (pin "2") (pinfunction "2_2") (pintype "input"))
      (node (ref "U31") (pin "1") (pinfunction "1_1") (pintype "unspecified"))
      (node (ref "U34") (pin "2") (pinfunction "2_2") (pintype "unspecified"))
    )
    (net (code "5") (name "/AC-") (class "Default")
      (node (ref "C19") (pin "1") (pinfunction "1_1") (pintype "unspecified"))
      (node (ref "H14") (pin "1") (pinfunction "1_1") (pintype "input"))
      (node (ref "H14") (pin "2") (pinfunction "2_2") (pintype "input"))
      (node (ref "R23") (pin "2") (pinfunction "2_2") (pintype "unspecified"))
      (node (ref "U40") (pin "2") (pinfunction "2_2") (pintype "unspecified"))
    )
    (net (code "6") (name "/ADC") (class "Default")
      (node (ref "H9") (pin "1") (pinfunction "1_1") (pintype "input"))
      (node (ref "U26") (pin "25") (pinfunction "PA0_25") (pintype "unspecified"))
    )
    (net (code "7") (name "/HO1") (class "Default")
      (node (ref "D7") (pin "1") (pinfunction "K_1") (pintype "unspecified"))
      (node (ref "H7") (pin "1") (pinfunction "1_1") (pintype "input"))
      (node (ref "R26") (pin "1") (pinfunction "1_1") (pintype "input"))
    )
    (net (code "8") (name "/HO2") (class "Default")
      (node (ref "D9") (pin "1") (pinfunction "K_1") (pintype "unspecified"))
      (node (ref "H8") (pin "1") (pinfunction "1_1") (pintype "input"))
      (node (ref "R30") (pin "1") (pinfunction "1_1") (pintype "input"))
    )
    (net (code "9") (name "/KEY") (class "Default")
      (node (ref "SW2") (pin "1") (pinfunction "A_1") (pintype "unspecified"))
      (node (ref "SW2") (pin "2") (pinfunction "B_2") (pintype "unspecified"))
      (node (ref "U26") (pin "34") (pinfunction "PB1_34") (pintype "unspecified"))
    )
    (net (code "10") (name "/LO1") (class "Default")
      (node (ref "D8") (pin "1") (pinfunction "K_1") (pintype "unspecified"))
      (node (ref "H7") (pin "3") (pinfunction "3_3") (pintype "input"))
      (node (ref "R28") (pin "1") (pinfunction "1_1") (pintype "input"))
    )
    (net (code "11") (name "/LO2") (class "Default")
      (node (ref "D10") (pin "1") (pinfunction "K_1") (pintype "unspecified"))
      (node (ref "H8") (pin "3") (pinfunction "3_3") (pintype "input"))
      (node (ref "R32") (pin "1") (pinfunction "1_1") (pintype "input"))
    )
    (net (code "12") (name "/PROTECT") (class "Default")
      (node (ref "R11") (pin "1") (pinfunction "1_1") (pintype "unspecified"))
      (node (ref "U26") (pin "33") (pinfunction "PB0_33") (pintype "unspecified"))
    )
    (net (code "13") (name "/PWM") (class "Default")
      (node (ref "R13") (pin "1") (pinfunction "1_1") (pintype "input"))
      (node (ref "U26") (pin "5") (pinfunction "PA8_5") (pintype "unspecified"))
    )
    (net (code "14") (name "/PWM_N") (class "Default")
      (node (ref "R15") (pin "1") (pinfunction "1_1") (pintype "input"))
      (node (ref "U26") (pin "2") (pinfunction "PB13_2") (pintype "unspecified"))
    )
    (net (code "15") (name "/PWM_SD") (class "Default")
      (node (ref "R14") (pin "1") (pinfunction "1_1") (pintype "input"))
      (node (ref "R16") (pin "1") (pinfunction "1_1") (pintype "input"))
      (node (ref "U26") (pin "6") (pinfunction "PA9_6") (pintype "unspecified"))
    )
    (net (code "16") (name "/SCL") (class "Default")
      (node (ref "U26") (pin "16") (pinfunction "PB8_16") (pintype "unspecified"))
      (node (ref "U27") (pin "3") (pinfunction "SCL_3") (pintype "unspecified"))
    )
    (net (code "17") (name "/SDA") (class "Default")
      (node (ref "U26") (pin "17") (pinfunction "PB9_17") (pintype "unspecified"))
      (node (ref "U27") (pin "4") (pinfunction "SDA_4") (pintype "unspecified"))
    )
    (net (code "18") (name "/VREF") (class "Default")
      (node (ref "R8") (pin "1") (pinfunction "1_1") (pintype "unspecified"))
      (node (ref "R9") (pin "2") (pinfunction "2_2") (pintype "unspecified"))
      (node (ref "U30") (pin "3") (pinfunction "IN_A+_3") (pintype "unspecified"))
    )
    (net (code "19") (name "/VS1") (class "Default")
      (node (ref "H7") (pin "2") (pinfunction "2_2") (pintype "input"))
      (node (ref "Q2") (pin "3") (pinfunction "S_3") (pintype "unspecified"))
      (node (ref "Q3") (pin "2") (pinfunction "D_2") (pintype "unspecified"))
      (node (ref "R25") (pin "2") (pinfunction "2_2") (pintype "input"))
      (node (ref "U34") (pin "1") (pinfunction "1_1") (pintype "unspecified"))
    )
    (net (code "20") (name "/VS2") (class "Default")
      (node (ref "H8") (pin "2") (pinfunction "2_2") (pintype "input"))
      (node (ref "Q4") (pin "3") (pinfunction "S_3") (pintype "unspecified"))
      (node (ref "Q5") (pin "2") (pinfunction "D_2") (pintype "unspecified"))
      (node (ref "R29") (pin "2") (pinfunction "2_2") (pintype "input"))
      (node (ref "U40") (pin "1") (pinfunction "1_1") (pintype "unspecified"))
    )
    (net (code "21") (name "AGND") (class "Default")
      (node (ref "C20") (pin "1") (pinfunction "1_1") (pintype "input"))
      (node (ref "C21") (pin "1") (pinfunction "1_1") (pintype "input"))
      (node (ref "H11") (pin "1") (pinfunction "1_1") (pintype "input"))
      (node (ref "H11") (pin "2") (pinfunction "2_2") (pintype "input"))
      (node (ref "H5") (pin "4") (pinfunction "4_4") (pintype "input"))
      (node (ref "H6") (pin "4") (pinfunction "4_4") (pintype "input"))
      (node (ref "H7") (pin "4") (pinfunction "4_4") (pintype "input"))
      (node (ref "H8") (pin "4") (pinfunction "4_4") (pintype "input"))
      (node (ref "Q3") (pin "3") (pinfunction "S_3") (pintype "unspecified"))
      (node (ref "Q5") (pin "3") (pinfunction "S_3") (pintype "unspecified"))
      (node (ref "R27") (pin "2") (pinfunction "2_2") (pintype "input"))
      (node (ref "R31") (pin "2") (pinfunction "2_2") (pintype "input"))
      (node (ref "R33") (pin "2") (pinfunction "2_2") (pintype "unspecified"))
      (node (ref "U41") (pin "2") (pinfunction "2_2") (pintype "input"))
      (node (ref "U42") (pin "2") (pinfunction "2_2") (pintype "input"))
    )
    (net (code "22") (name "GND") (class "Default")
      (node (ref "C1") (pin "1") (pinfunction "1_1") (pintype "unspecified"))
      (node (ref "C10") (pin "1") (pinfunction "1_1") (pintype "input"))
      (node (ref "C11") (pin "2") (pinfunction "2_2") (pintype "input"))
      (node (ref "C12") (pin "1") (pinfunction "1_1") (pintype "input"))
      (node (ref "C13") (pin "1") (pinfunction "1_1") (pintype "input"))
      (node (ref "C16") (pin "1") (pinfunction "1_1") (pintype "unspecified"))
      (node (ref "C17") (pin "1") (pinfunction "1_1") (pintype "input"))
      (node (ref "C18") (pin "1") (pinfunction "1_1") (pintype "input"))
      (node (ref "C22") (pin "2") (pinfunction "2_2") (pintype "input"))
      (node (ref "C3") (pin "1") (pinfunction "1_1") (pintype "input"))
      (node (ref "C7") (pin "1") (pinfunction "1_1") (pintype "input"))
      (node (ref "C8") (pin "1") (pinfunction "1_1") (pintype "unspecified"))
      (node (ref "C9") (pin "1") (pinfunction "1_1") (pintype "unspecified"))
      (node (ref "D2") (pin "1") (pinfunction "A_1") (pintype "unspecified"))
      (node (ref "D6") (pin "2") (pinfunction "A_2") (pintype "unspecified"))
      (node (ref "DC1") (pin "2") (pinfunction "2_2") (pintype "unspecified"))
      (node (ref "DC1") (pin "3") (pinfunction "3_3") (pintype "unspecified"))
      (node (ref "H15") (pin "1") (pinfunction "1_1") (pintype "input"))
      (node (ref "H15") (pin "2") (pinfunction "2_2") (pintype "input"))
      (node (ref "H15") (pin "3") (pinfunction "3_3") (pintype "input"))
      (node (ref "H15") (pin "4") (pinfunction "4_4") (pintype "input"))
      (node (ref "H18") (pin "1") (pinfunction "1_1") (pintype "input"))
      (node (ref "H18") (pin "2") (pinfunction "2_2") (pintype "input"))
      (node (ref "H18") (pin "3") (pinfunction "3_3") (pintype "input"))
      (node (ref "H18") (pin "4") (pinfunction "4_4") (pintype "input"))
      (node (ref "Q1") (pin "2") (pinfunction "E_2") (pintype "unspecified"))
      (node (ref "R12") (pin "2") (pinfunction "2_2") (pintype "unspecified"))
      (node (ref "R18") (pin "2") (pinfunction "2_2") (pintype "unspecified"))
      (node (ref "R19") (pin "1") (pinfunction "1_1") (pintype "unspecified"))
      (node (ref "R3") (pin "1") (pinfunction "1_1") (pintype "unspecified"))
      (node (ref "R33") (pin "1") (pinfunction "1_1") (pintype "unspecified"))
      (node (ref "R4") (pin "1") (pinfunction "1_1") (pintype "unspecified"))
      (node (ref "R5") (pin "1") (pinfunction "1_1") (pintype "unspecified"))
      (node (ref "R9") (pin "1") (pinfunction "1_1") (pintype "unspecified"))
      (node (ref "SW2") (pin "3") (pinfunction "C_3") (pintype "unspecified"))
      (node (ref "SW2") (pin "4") (pinfunction "D_4") (pintype "unspecified"))
      (node (ref "U1") (pin "5") (pinfunction "GND_5") (pintype "unspecified"))
      (node (ref "U1") (pin "9") (pinfunction "PGND_9") (pintype "unspecified"))
      (node (ref "U24") (pin "3") (pinfunction "A_3") (pintype "unspecified"))
      (node (ref "U25") (pin "1") (pinfunction "GND_1") (pintype "unspecified"))
      (node (ref "U26") (pin "19") (pinfunction "GND_19") (pintype "unspecified"))
      (node (ref "U26") (pin "39") (pinfunction "GND_39") (pintype "unspecified"))
      (node (ref "U26") (pin "40") (pinfunction "GND_40") (pintype "unspecified"))
      (node (ref "U27") (pin "1") (pinfunction "GND_1") (pintype "unspecified"))
      (node (ref "U28") (pin "4") (pinfunction "COM_4") (pintype "unspecified"))
      (node (ref "U29") (pin "4") (pinfunction "COM_4") (pintype "unspecified"))
      (node (ref "U30") (pin "4") (pinfunction "V-_4") (pintype "unspecified"))
    )
    (net (code "23") (name "Net-(C5-Pad1)") (class "Default")
      (node (ref "C5") (pin "1") (pinfunction "1_1") (pintype "unspecified"))
      (node (ref "R4") (pin "2") (pinfunction "2_2") (pintype "unspecified"))
    )
    (net (code "24") (name "Net-(C22-Pad1)") (class "Default")
      (node (ref "C22") (pin "1") (pinfunction "1_1") (pintype "input"))
      (node (ref "H13") (pin "1") (pinfunction "1_1") (pintype "input"))
      (node (ref "H13") (pin "2") (pinfunction "2_2") (pintype "input"))
      (node (ref "L2") (pin "2") (pinfunction "2_2") (pintype "unspecified"))
    )
    (net (code "25") (name "Net-(D2-K)") (class "Default")
      (node (ref "C4") (pin "2") (pinfunction "2_2") (pintype "input"))
      (node (ref "D2") (pin "2") (pinfunction "K_2") (pintype "unspecified"))
      (node (ref "L1") (pin "1") (pinfunction "1_1") (pintype "unspecified"))
      (node (ref "U1") (pin "1") (pinfunction "SW_1") (pintype "unspecified"))
    )
    (net (code "26") (name "Net-(D3-A)") (class "Default")
      (node (ref "D3") (pin "2") (pinfunction "A_2") (pintype "unspecified"))
      (node (ref "LED1") (pin "2") (pinfunction "-_2") (pintype "unspecified"))
      (node (ref "Q1") (pin "3") (pinfunction "C_3") (pintype "unspecified"))
      (node (ref "RLY1") (pin "4") (pinfunction "4_4") (pintype "input"))
    )
    (net (code "27") (name "Net-(D4-K)") (class "Default")
      (node (ref "C14") (pin "1") (pinfunction "1_1") (pintype "unspecified"))
      (node (ref "D4") (pin "2") (pinfunction "K_2") (pintype "unspecified"))
      (node (ref "U28") (pin "8") (pinfunction "VB_8") (pintype "unspecified"))
    )
    (net (code "28") (name "Net-(D5-K)") (class "Default")
      (node (ref "C15") (pin "1") (pinfunction "1_1") (pintype "unspecified"))
      (node (ref "D5") (pin "2") (pinfunction "K_2") (pintype "unspecified"))
      (node (ref "U29") (pin "8") (pinfunction "VB_8") (pintype "unspecified"))
    )
    (net (code "29") (name "Net-(D6-K)") (class "Default")
      (node (ref "C18") (pin "2") (pinfunction "2_2") (pintype "input"))
      (node (ref "D6") (pin "1") (pinfunction "K_1") (pintype "unspecified"))
      (node (ref "H9") (pin "2") (pinfunction "2_2") (pintype "input"))
      (node (ref "R21") (pin "2") (pinfunction "2_2") (pintype "unspecified"))
    )
    (net (code "30") (name "Net-(D7-A)") (class "Default")
      (node (ref "D7") (pin "2") (pinfunction "A_2") (pintype "unspecified"))
      (node (ref "Q2") (pin "1") (pinfunction "G_1") (pintype "unspecified"))
      (node (ref "R25") (pin "1") (pinfunction "1_1") (pintype "input"))
      (node (ref "R26") (pin "2") (pinfunction "2_2") (pintype "input"))
    )
    (net (code "31") (name "Net-(D8-A)") (class "Default")
      (node (ref "D8") (pin "2") (pinfunction "A_2") (pintype "unspecified"))
      (node (ref "Q3") (pin "1") (pinfunction "G_1") (pintype "unspecified"))
      (node (ref "R27") (pin "1") (pinfunction "1_1") (pintype "input"))
      (node (ref "R28") (pin "2") (pinfunction "2_2") (pintype "input"))
    )
    (net (code "32") (name "Net-(D9-A)") (class "Default")
      (node (ref "D9") (pin "2") (pinfunction "A_2") (pintype "unspecified"))
      (node (ref "Q4") (pin "1") (pinfunction "G_1") (pintype "unspecified"))
      (node (ref "R29") (pin "1") (pinfunction "1_1") (pintype "input"))
      (node (ref "R30") (pin "2") (pinfunction "2_2") (pintype "input"))
    )
    (net (code "33") (name "Net-(D10-A)") (class "Default")
      (node (ref "D10") (pin "2") (pinfunction "A_2") (pintype "unspecified"))
      (node (ref "Q5") (pin "1") (pinfunction "G_1") (pintype "unspecified"))
      (node (ref "R31") (pin "1") (pinfunction "1_1") (pintype "input"))
      (node (ref "R32") (pin "2") (pinfunction "2_2") (pintype "input"))
    )
    (net (code "34") (name "Net-(H4-Pad1)") (class "Default")
      (node (ref "H4") (pin "1") (pinfunction "1_1") (pintype "input"))
      (node (ref "H4") (pin "2") (pinfunction "2_2") (pintype "input"))
      (node (ref "RLY1") (pin "5") (pinfunction "5_5") (pintype "input"))
    )
    (net (code "35") (name "Net-(H12-Pad1)") (class "Default")
      (node (ref "H12") (pin "1") (pinfunction "1_1") (pintype "input"))
      (node (ref "H12") (pin "2") (pinfunction "2_2") (pintype "input"))
      (node (ref "R34") (pin "1") (pinfunction "1_1") (pintype "unspecified"))
    )
    (net (code "36") (name "Net-(L2-Pad1)") (class "Default")
      (node (ref "L2") (pin "1") (pinfunction "1_1") (pintype "unspecified"))
      (node (ref "R34") (pin "2") (pinfunction "2_2") (pintype "unspecified"))
    )
    (net (code "37") (name "Net-(LED1-+)") (class "Default")
      (node (ref "LED1") (pin "1") (pinfunction "+_1") (pintype "unspecified"))
      (node (ref "R10") (pin "2") (pinfunction "2_2") (pintype "unspecified"))
    )
    (net (code "38") (name "Net-(Q1-B)") (class "Default")
      (node (ref "Q1") (pin "1") (pinfunction "B_1") (pintype "unspecified"))
      (node (ref "R11") (pin "2") (pinfunction "2_2") (pintype "unspecified"))
      (node (ref "R12") (pin "1") (pinfunction "1_1") (pintype "unspecified"))
    )
    (net (code "39") (name "Net-(R22-Pad2)") (class "Default")
      (node (ref "R22") (pin "2") (pinfunction "2_2") (pintype "unspecified"))
      (node (ref "R24") (pin "1") (pinfunction "1_1") (pintype "unspecified"))
      (node (ref "U31") (pin "4") (pinfunction "4_4") (pintype "unspecified"))
    )
    (net (code "40") (name "Net-(R23-Pad1)") (class "Default")
      (node (ref "R23") (pin "1") (pinfunction "1_1") (pintype "unspecified"))
      (node (ref "U31") (pin "2") (pinfunction "2_2") (pintype "unspecified"))
    )
    (net (code "41") (name "Net-(R24-Pad2)") (class "Default")
      (node (ref "R24") (pin "2") (pinfunction "2_2") (pintype "unspecified"))
      (node (ref "U31") (pin "3") (pinfunction "3_3") (pintype "unspecified"))
    )
    (net (code "42") (name "Net-(U1-BST)") (class "Default")
      (node (ref "C4") (pin "1") (pinfunction "1_1") (pintype "input"))
      (node (ref "U1") (pin "8") (pinfunction "BST_8") (pintype "unspecified"))
    )
    (net (code "43") (name "Net-(U1-COMP)") (class "Default")
      (node (ref "C5") (pin "2") (pinfunction "2_2") (pintype "unspecified"))
      (node (ref "U1") (pin "3") (pinfunction "COMP_3") (pintype "unspecified"))
    )
    (net (code "44") (name "Net-(U1-FB)") (class "Default")
      (node (ref "R5") (pin "2") (pinfunction "2_2") (pintype "unspecified"))
      (node (ref "R6") (pin "1") (pinfunction "1_1") (pintype "unspecified"))
      (node (ref "U1") (pin "4") (pinfunction "FB_4") (pintype "unspecified"))
    )
    (net (code "45") (name "Net-(U1-FREQ)") (class "Default")
      (node (ref "R3") (pin "2") (pinfunction "2_2") (pintype "unspecified"))
      (node (ref "U1") (pin "6") (pinfunction "FREQ_6") (pintype "unspecified"))
    )
    (net (code "46") (name "Net-(U24-K)") (class "Default")
      (node (ref "R7") (pin "1") (pinfunction "1_1") (pintype "unspecified"))
      (node (ref "R8") (pin "2") (pinfunction "2_2") (pintype "unspecified"))
      (node (ref "U24") (pin "1") (pinfunction "R_1") (pintype "unspecified"))
      (node (ref "U24") (pin "2") (pinfunction "K_2") (pintype "unspecified"))
    )
    (net (code "47") (name "Net-(U28-HO)") (class "Default")
      (node (ref "H5") (pin "1") (pinfunction "1_1") (pintype "input"))
      (node (ref "U28") (pin "7") (pinfunction "HO_7") (pintype "unspecified"))
    )
    (net (code "48") (name "Net-(U28-IN)") (class "Default")
      (node (ref "R13") (pin "2") (pinfunction "2_2") (pintype "input"))
      (node (ref "U28") (pin "2") (pinfunction "IN_2") (pintype "unspecified"))
    )
    (net (code "49") (name "Net-(U28-LO)") (class "Default")
      (node (ref "H5") (pin "3") (pinfunction "3_3") (pintype "input"))
      (node (ref "U28") (pin "5") (pinfunction "LO_5") (pintype "unspecified"))
    )
    (net (code "50") (name "Net-(U28-SD#)") (class "Default")
      (node (ref "R14") (pin "2") (pinfunction "2_2") (pintype "input"))
      (node (ref "U28") (pin "3") (pinfunction "SD#_3") (pintype "unspecified"))
    )
    (net (code "51") (name "Net-(U28-VS)") (class "Default")
      (node (ref "C14") (pin "2") (pinfunction "2_2") (pintype "unspecified"))
      (node (ref "H5") (pin "2") (pinfunction "2_2") (pintype "input"))
      (node (ref "U28") (pin "6") (pinfunction "VS_6") (pintype "unspecified"))
    )
    (net (code "52") (name "Net-(U29-HO)") (class "Default")
      (node (ref "H6") (pin "1") (pinfunction "1_1") (pintype "input"))
      (node (ref "U29") (pin "7") (pinfunction "HO_7") (pintype "unspecified"))
    )
    (net (code "53") (name "Net-(U29-IN)") (class "Default")
      (node (ref "R15") (pin "2") (pinfunction "2_2") (pintype "input"))
      (node (ref "U29") (pin "2") (pinfunction "IN_2") (pintype "unspecified"))
    )
    (net (code "54") (name "Net-(U29-LO)") (class "Default")
      (node (ref "H6") (pin "3") (pinfunction "3_3") (pintype "input"))
      (node (ref "U29") (pin "5") (pinfunction "LO_5") (pintype "unspecified"))
    )
    (net (code "55") (name "Net-(U29-SD#)") (class "Default")
      (node (ref "R16") (pin "2") (pinfunction "2_2") (pintype "input"))
      (node (ref "U29") (pin "3") (pinfunction "SD#_3") (pintype "unspecified"))
    )
    (net (code "56") (name "Net-(U29-VS)") (class "Default")
      (node (ref "C15") (pin "2") (pinfunction "2_2") (pintype "unspecified"))
      (node (ref "H6") (pin "2") (pinfunction "2_2") (pintype "input"))
      (node (ref "U29") (pin "6") (pinfunction "VS_6") (pintype "unspecified"))
    )
    (net (code "57") (name "Net-(U30A-IN_A-)") (class "Default")
      (node (ref "R17") (pin "2") (pinfunction "2_2") (pintype "unspecified"))
      (node (ref "U30") (pin "1") (pinfunction "OUT_A_1") (pintype "output"))
      (node (ref "U30") (pin "2") (pinfunction "IN_A-_2") (pintype "unspecified"))
    )
    (net (code "58") (name "Net-(U30B-IN_B+)") (class "Default")
      (node (ref "R17") (pin "1") (pinfunction "1_1") (pintype "unspecified"))
      (node (ref "R18") (pin "1") (pinfunction "1_1") (pintype "unspecified"))
      (node (ref "R22") (pin "1") (pinfunction "1_1") (pintype "unspecified"))
      (node (ref "U30") (pin "5") (pinfunction "IN_B+_5") (pintype "unspecified"))
    )
    (net (code "59") (name "Net-(U30B-IN_B-)") (class "Default")
      (node (ref "R19") (pin "2") (pinfunction "2_2") (pintype "unspecified"))
      (node (ref "R20") (pin "2") (pinfunction "2_2") (pintype "unspecified"))
      (node (ref "U30") (pin "6") (pinfunction "IN_B-_6") (pintype "unspecified"))
    )
    (net (code "60") (name "Net-(U30B-OUT_B)") (class "Default")
      (node (ref "R20") (pin "1") (pinfunction "1_1") (pintype "unspecified"))
      (node (ref "R21") (pin "1") (pinfunction "1_1") (pintype "unspecified"))
      (node (ref "U30") (pin "7") (pinfunction "OUT_B_7") (pintype "output"))
    )
    (net (code "61") (name "VCC") (class "Default")
      (node (ref "C20") (pin "2") (pinfunction "2_2") (pintype "input"))
      (node (ref "C21") (pin "2") (pinfunction "2_2") (pintype "input"))
      (node (ref "Q2") (pin "2") (pinfunction "D_2") (pintype "unspecified"))
      (node (ref "Q4") (pin "2") (pinfunction "D_2") (pintype "unspecified"))
      (node (ref "RLY1") (pin "2") (pinfunction "2_2") (pintype "input"))
      (node (ref "U41") (pin "1") (pinfunction "1_1") (pintype "input"))
      (node (ref "U42") (pin "1") (pinfunction "1_1") (pintype "input"))
    )
    (net (code "62") (name "VIN") (class "Default")
      (node (ref "DC1") (pin "1") (pinfunction "1_1") (pintype "unspecified"))
      (node (ref "SW1") (pin "6") (pinfunction "6_6") (pintype "unspecified"))
    )
    (net (code "63") (name "unconnected-(RLY1-Pad3)") (class "Default")
      (node (ref "RLY1") (pin "3") (pinfunction "3_3") (pintype "input+no_connect"))
    )
    (net (code "64") (name "unconnected-(SW1-Pad1)") (class "Default")
      (node (ref "SW1") (pin "1") (pinfunction "1_1") (pintype "unspecified+no_connect"))
    )
    (net (code "65") (name "unconnected-(SW1-Pad2)") (class "Default")
      (node (ref "SW1") (pin "2") (pinfunction "2_2") (pintype "unspecified+no_connect"))
    )
    (net (code "66") (name "unconnected-(SW1-Pad3)") (class "Default")
      (node (ref "SW1") (pin "3") (pinfunction "3_3") (pintype "unspecified+no_connect"))
    )
    (net (code "67") (name "unconnected-(SW1-Pad4)") (class "Default")
      (node (ref "SW1") (pin "4") (pinfunction "4_4") (pintype "unspecified+no_connect"))
    )
    (net (code "68") (name "unconnected-(TP1-Pad1)") (class "Default")
      (node (ref "TP1") (pin "1") (pinfunction "1_1") (pintype "input+no_connect"))
    )
    (net (code "69") (name "unconnected-(TP2-Pad1)") (class "Default")
      (node (ref "TP2") (pin "1") (pinfunction "1_1") (pintype "input+no_connect"))
    )
    (net (code "70") (name "unconnected-(TP3-Pad1)") (class "Default")
      (node (ref "TP3") (pin "1") (pinfunction "1_1") (pintype "input+no_connect"))
    )
    (net (code "71") (name "unconnected-(TP4-Pad1)") (class "Default")
      (node (ref "TP4") (pin "1") (pinfunction "1_1") (pintype "input+no_connect"))
    )
    (net (code "72") (name "unconnected-(U1-EN-Pad2)") (class "Default")
      (node (ref "U1") (pin "2") (pinfunction "EN_2") (pintype "unspecified+no_connect"))
    )
    (net (code "73") (name "unconnected-(U26-+3.3V-Pad20)") (class "Default")
      (node (ref "U26") (pin "20") (pinfunction "+3.3V_20") (pintype "unspecified+no_connect"))
    )
    (net (code "74") (name "unconnected-(U26-+5V-Pad18)") (class "Default")
      (node (ref "U26") (pin "18") (pinfunction "+5V_18") (pintype "unspecified+no_connect"))
    )
    (net (code "75") (name "unconnected-(U26-PA1-Pad26)") (class "Default")
      (node (ref "U26") (pin "26") (pinfunction "PA1_26") (pintype "unspecified+no_connect"))
    )
    (net (code "76") (name "unconnected-(U26-PA2-Pad27)") (class "Default")
      (node (ref "U26") (pin "27") (pinfunction "PA2_27") (pintype "unspecified+no_connect"))
    )
    (net (code "77") (name "unconnected-(U26-PA3-Pad28)") (class "Default")
      (node (ref "U26") (pin "28") (pinfunction "PA3_28") (pintype "unspecified+no_connect"))
    )
    (net (code "78") (name "unconnected-(U26-PA4-Pad29)") (class "Default")
      (node (ref "U26") (pin "29") (pinfunction "PA4_29") (pintype "unspecified+no_connect"))
    )
    (net (code "79") (name "unconnected-(U26-PA5-Pad30)") (class "Default")
      (node (ref "U26") (pin "30") (pinfunction "PA5_30") (pintype "unspecified+no_connect"))
    )
    (net (code "80") (name "unconnected-(U26-PA6-Pad31)") (class "Default")
      (node (ref "U26") (pin "31") (pinfunction "PA6_31") (pintype "unspecified+no_connect"))
    )
    (net (code "81") (name "unconnected-(U26-PA7-Pad32)") (class "Default")
      (node (ref "U26") (pin "32") (pinfunction "PA7_32") (pintype "unspecified+no_connect"))
    )
    (net (code "82") (name "unconnected-(U26-PA10-Pad7)") (class "Default")
      (node (ref "U26") (pin "7") (pinfunction "PA10_7") (pintype "unspecified+no_connect"))
    )
    (net (code "83") (name "unconnected-(U26-PA11-Pad8)") (class "Default")
      (node (ref "U26") (pin "8") (pinfunction "PA11_8") (pintype "unspecified+no_connect"))
    )
    (net (code "84") (name "unconnected-(U26-PA12-Pad9)") (class "Default")
      (node (ref "U26") (pin "9") (pinfunction "PA12_9") (pintype "unspecified+no_connect"))
    )
    (net (code "85") (name "unconnected-(U26-PA15-Pad10)") (class "Default")
      (node (ref "U26") (pin "10") (pinfunction "PA15_10") (pintype "unspecified+no_connect"))
    )
    (net (code "86") (name "unconnected-(U26-PB3-Pad11)") (class "Default")
      (node (ref "U26") (pin "11") (pinfunction "PB3_11") (pintype "unspecified+no_connect"))
    )
    (net (code "87") (name "unconnected-(U26-PB4-Pad12)") (class "Default")
      (node (ref "U26") (pin "12") (pinfunction "PB4_12") (pintype "unspecified+no_connect"))
    )
    (net (code "88") (name "unconnected-(U26-PB5-Pad13)") (class "Default")
      (node (ref "U26") (pin "13") (pinfunction "PB5_13") (pintype "unspecified+no_connect"))
    )
    (net (code "89") (name "unconnected-(U26-PB6-Pad14)") (class "Default")
      (node (ref "U26") (pin "14") (pinfunction "PB6_14") (pintype "unspecified+no_connect"))
    )
    (net (code "90") (name "unconnected-(U26-PB7-Pad15)") (class "Default")
      (node (ref "U26") (pin "15") (pinfunction "PB7_15") (pintype "unspecified+no_connect"))
    )
    (net (code "91") (name "unconnected-(U26-PB10-Pad35)") (class "Default")
      (node (ref "U26") (pin "35") (pinfunction "PB10_35") (pintype "unspecified+no_connect"))
    )
    (net (code "92") (name "unconnected-(U26-PB11-Pad36)") (class "Default")
      (node (ref "U26") (pin "36") (pinfunction "PB11_36") (pintype "unspecified+no_connect"))
    )
    (net (code "93") (name "unconnected-(U26-PB12-Pad1)") (class "Default")
      (node (ref "U26") (pin "1") (pinfunction "PB12_1") (pintype "unspecified+no_connect"))
    )
    (net (code "94") (name "unconnected-(U26-PB14-Pad3)") (class "Default")
      (node (ref "U26") (pin "3") (pinfunction "PB14_3") (pintype "unspecified+no_connect"))
    )
    (net (code "95") (name "unconnected-(U26-PB15-Pad4)") (class "Default")
      (node (ref "U26") (pin "4") (pinfunction "PB15_4") (pintype "unspecified+no_connect"))
    )
    (net (code "96") (name "unconnected-(U26-PC13-Pad22)") (class "Default")
      (node (ref "U26") (pin "22") (pinfunction "PC13_22") (pintype "unspecified+no_connect"))
    )
    (net (code "97") (name "unconnected-(U26-PC14-Pad23)") (class "Default")
      (node (ref "U26") (pin "23") (pinfunction "PC14_23") (pintype "unspecified+no_connect"))
    )
    (net (code "98") (name "unconnected-(U26-PC15-Pad24)") (class "Default")
      (node (ref "U26") (pin "24") (pinfunction "PC15_24") (pintype "unspecified+no_connect"))
    )
    (net (code "99") (name "unconnected-(U26-RESET-Pad37)") (class "Default")
      (node (ref "U26") (pin "37") (pinfunction "RESET_37") (pintype "unspecified+no_connect"))
    )
    (net (code "100") (name "unconnected-(U26-VBAT-Pad21)") (class "Default")
      (node (ref "U26") (pin "21") (pinfunction "VBAT_21") (pintype "unspecified+no_connect"))
    )
  )
)
